# DAC.net
KiCad netlist of a schematic drawn in Altium Designer
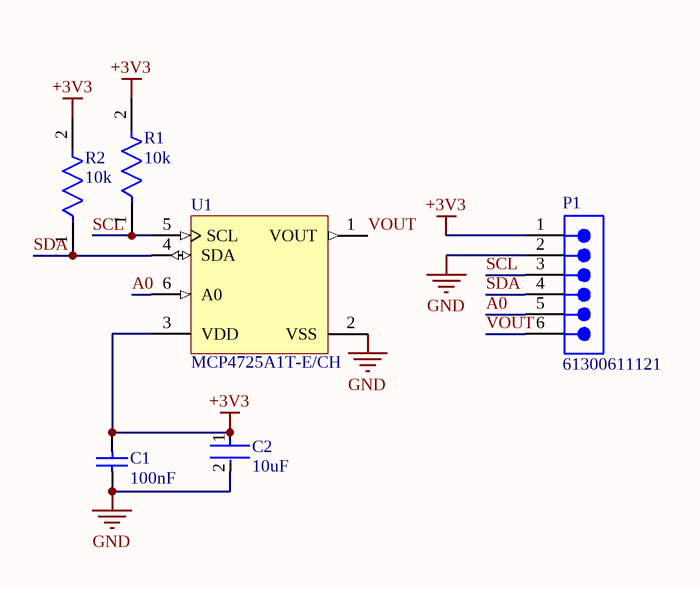
[diagram p0: DAC.SchDoc]

(export (version "E")
  (design (tool "Eeschema 10.0.6"))
  (components
    (comp (ref "C1")
      (value "100nF")
      (footprint "CAPC1050X55X23ML05T13")
      (description "Chip Capacitor, 100 nF, +/- 10%, 16 V, -55 to 125 degC, 0402 (1005 Metric), RoHS, Tape and Reel")
      (fields (field (name "MANUFACTURER") "Samsung Electro-Mechanics"))
      (libsource (lib "Altium Content Vault") (part "CAP-NP-2"))
    )
    (comp (ref "C2")
      (value "10uF")
      (footprint "FP-C0805C106J8RACAUTO-MFG")
      (description "CAP CER 10UF 10V X7R 0805")
      (fields (field (name "TOLERANCE") "5%"))
      (libsource (lib "Altium Content Vault") (part "02cd4be3c70576c341d710602a673aa"))
    )
    (comp (ref "P1")
      (value "61300611121")
      (footprint "61300611121")
      (libsource (lib "Altium Content Vault") (part "Header_Male_1R_06P"))
    )
    (comp (ref "R1")
      (value "10k")
      (footprint "FP-CRCW0402-C-e3-IPC_C")
      (description "RES 10K OHM 1% 1/16W 0402")
      (fields (field (name "TOLERANCE") "1%"))
      (libsource (lib "Altium Content Vault") (part "1029c3af85768c4190bb7ad29bc67b5"))
    )
    (comp (ref "R2")
      (value "10k")
      (footprint "FP-CRCW0402-C-e3-IPC_C")
      (description "RES 10K OHM 1% 1/16W 0402")
      (fields (field (name "TOLERANCE") "1%"))
      (libsource (lib "Altium Content Vault") (part "1029c3af85768c4190bb7ad29bc67b5"))
    )
    (comp (ref "U1")
      (value "MCP4725A1T-E/CH")
      (footprint "SOT-23-CH6_N")
      (libsource (lib "Altium Content Vault") (part "CON-DAC-MCP4725-6"))
    )
  )
  (nets
    (net (code "1") (name "+3V3") (class "Default")
      (node (ref "C1") (pin "2") (pinfunction "2_2") (pintype "passive"))
      (node (ref "C2") (pin "1") (pinfunction "1_1") (pintype "passive"))
      (node (ref "P1") (pin "1") (pinfunction "1_1") (pintype "passive"))
      (node (ref "R1") (pin "2") (pinfunction "2_2") (pintype "passive"))
      (node (ref "R2") (pin "2") (pinfunction "2_2") (pintype "passive"))
      (node (ref "U1") (pin "3") (pinfunction "VDD_3") (pintype "power_in"))
    )
    (net (code "2") (name "/A0") (class "Default")
      (node (ref "P1") (pin "5") (pinfunction "5_5") (pintype "passive"))
      (node (ref "U1") (pin "6") (pinfunction "A0_6") (pintype "input"))
    )
    (net (code "3") (name "/SCL") (class "Default")
      (node (ref "P1") (pin "3") (pinfunction "3_3") (pintype "passive"))
      (node (ref "R1") (pin "1") (pinfunction "1_1") (pintype "passive"))
      (node (ref "U1") (pin "5") (pinfunction "SCL_5") (pintype "input"))
    )
    (net (code "4") (name "/SDA") (class "Default")
      (node (ref "P1") (pin "4") (pinfunction "4_4") (pintype "passive"))
      (node (ref "R2") (pin "1") (pinfunction "1_1") (pintype "passive"))
      (node (ref "U1") (pin "4") (pinfunction "SDA_4") (pintype "bidirectional"))
    )
    (net (code "5") (name "/VOUT") (class "Default")
      (node (ref "P1") (pin "6") (pinfunction "6_6") (pintype "passive"))
      (node (ref "U1") (pin "1") (pinfunction "VOUT_1") (pintype "output"))
    )
    (net (code "6") (name "GND") (class "Default")
      (node (ref "C1") (pin "1") (pinfunction "1_1") (pintype "passive"))
      (node (ref "C2") (pin "2") (pinfunction "2_2") (pintype "passive"))
      (node (ref "P1") (pin "2") (pinfunction "2_2") (pintype "passive"))
      (node (ref "U1") (pin "2") (pinfunction "VSS_2") (pintype "power_in"))
    )
  )
)
